# LuMini_2Inch.net
KiCad netlist of a schematic drawn in EAGLE
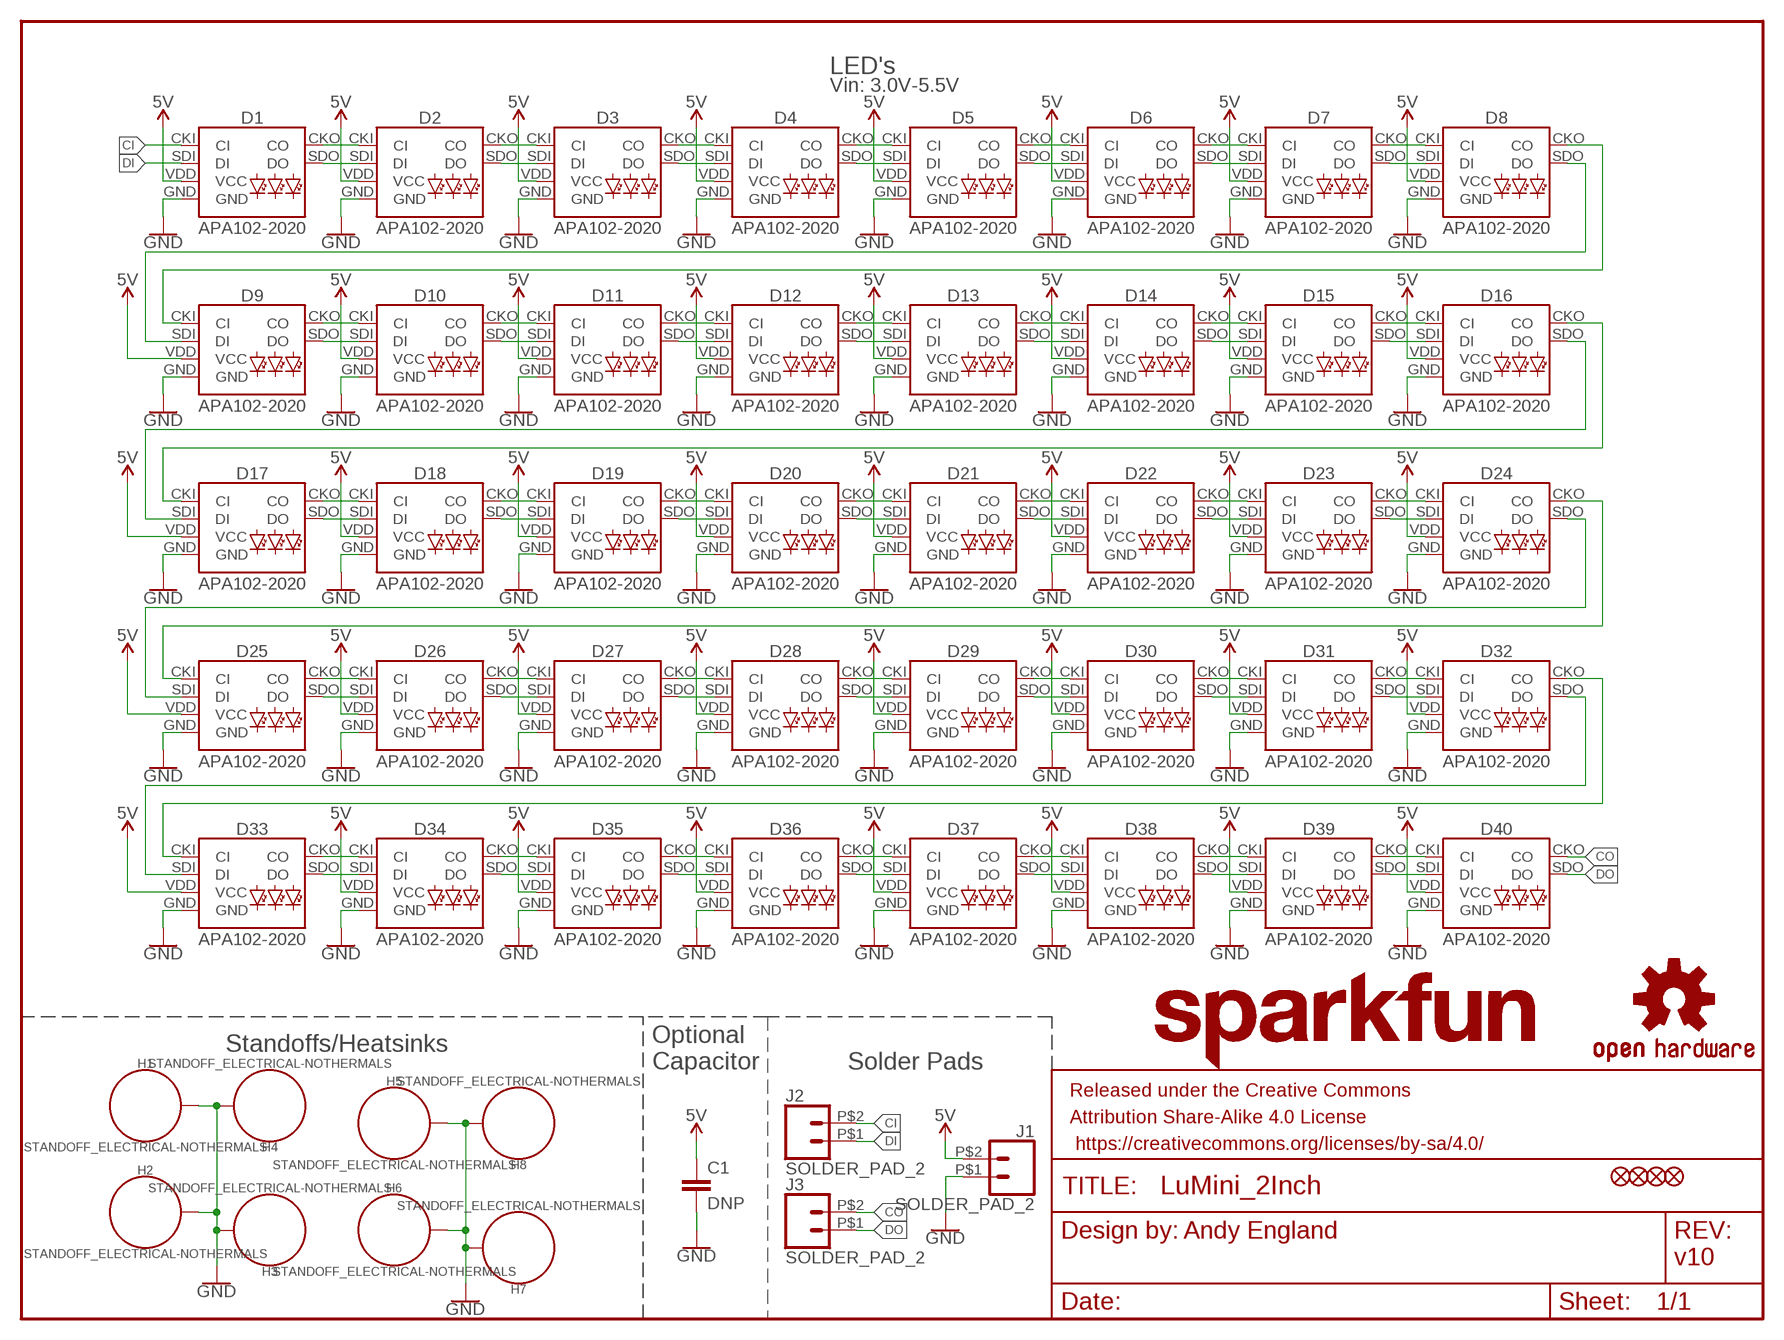
[diagram p0: schematic, sheet 1]

(export (version "E")
  (design (tool "Eeschema 10.0.6"))
  (components
    (comp (ref "C1")
      (value "DNP")
      (footprint "eagle-import:1206")
      (libsource (lib "eagle-import") (part "4.7UF-1206-16V-(+80/-20%)"))
    )
    (comp (ref "D1")
      (value "APA102-2020")
      (footprint "eagle-import:APA102-2020")
      (libsource (lib "eagle-import") (part "APA102-2020"))
    )
    (comp (ref "D2")
      (value "APA102-2020")
      (footprint "eagle-import:APA102-2020")
      (libsource (lib "eagle-import") (part "APA102-2020"))
    )
    (comp (ref "D3")
      (value "APA102-2020")
      (footprint "eagle-import:APA102-2020")
      (libsource (lib "eagle-import") (part "APA102-2020"))
    )
    (comp (ref "D4")
      (value "APA102-2020")
      (footprint "eagle-import:APA102-2020")
      (libsource (lib "eagle-import") (part "APA102-2020"))
    )
    (comp (ref "D5")
      (value "APA102-2020")
      (footprint "eagle-import:APA102-2020")
      (libsource (lib "eagle-import") (part "APA102-2020"))
    )
    (comp (ref "D6")
      (value "APA102-2020")
      (footprint "eagle-import:APA102-2020")
      (libsource (lib "eagle-import") (part "APA102-2020"))
    )
    (comp (ref "D7")
      (value "APA102-2020")
      (footprint "eagle-import:APA102-2020")
      (libsource (lib "eagle-import") (part "APA102-2020"))
    )
    (comp (ref "D8")
      (value "APA102-2020")
      (footprint "eagle-import:APA102-2020")
      (libsource (lib "eagle-import") (part "APA102-2020"))
    )
    (comp (ref "D9")
      (value "APA102-2020")
      (footprint "eagle-import:APA102-2020")
      (libsource (lib "eagle-import") (part "APA102-2020"))
    )
    (comp (ref "D10")
      (value "APA102-2020")
      (footprint "eagle-import:APA102-2020")
      (libsource (lib "eagle-import") (part "APA102-2020"))
    )
    (comp (ref "D11")
      (value "APA102-2020")
      (footprint "eagle-import:APA102-2020")
      (libsource (lib "eagle-import") (part "APA102-2020"))
    )
    (comp (ref "D12")
      (value "APA102-2020")
      (footprint "eagle-import:APA102-2020")
      (libsource (lib "eagle-import") (part "APA102-2020"))
    )
    (comp (ref "D13")
      (value "APA102-2020")
      (footprint "eagle-import:APA102-2020")
      (libsource (lib "eagle-import") (part "APA102-2020"))
    )
    (comp (ref "D14")
      (value "APA102-2020")
      (footprint "eagle-import:APA102-2020")
      (libsource (lib "eagle-import") (part "APA102-2020"))
    )
    (comp (ref "D15")
      (value "APA102-2020")
      (footprint "eagle-import:APA102-2020")
      (libsource (lib "eagle-import") (part "APA102-2020"))
    )
    (comp (ref "D16")
      (value "APA102-2020")
      (footprint "eagle-import:APA102-2020")
      (libsource (lib "eagle-import") (part "APA102-2020"))
    )
    (comp (ref "D17")
      (value "APA102-2020")
      (footprint "eagle-import:APA102-2020")
      (libsource (lib "eagle-import") (part "APA102-2020"))
    )
    (comp (ref "D18")
      (value "APA102-2020")
      (footprint "eagle-import:APA102-2020")
      (libsource (lib "eagle-import") (part "APA102-2020"))
    )
    (comp (ref "D19")
      (value "APA102-2020")
      (footprint "eagle-import:APA102-2020")
      (libsource (lib "eagle-import") (part "APA102-2020"))
    )
    (comp (ref "D20")
      (value "APA102-2020")
      (footprint "eagle-import:APA102-2020")
      (libsource (lib "eagle-import") (part "APA102-2020"))
    )
    (comp (ref "D21")
      (value "APA102-2020")
      (footprint "eagle-import:APA102-2020")
      (libsource (lib "eagle-import") (part "APA102-2020"))
    )
    (comp (ref "D22")
      (value "APA102-2020")
      (footprint "eagle-import:APA102-2020")
      (libsource (lib "eagle-import") (part "APA102-2020"))
    )
    (comp (ref "D23")
      (value "APA102-2020")
      (footprint "eagle-import:APA102-2020")
      (libsource (lib "eagle-import") (part "APA102-2020"))
    )
    (comp (ref "D24")
      (value "APA102-2020")
      (footprint "eagle-import:APA102-2020")
      (libsource (lib "eagle-import") (part "APA102-2020"))
    )
    (comp (ref "D25")
      (value "APA102-2020")
      (footprint "eagle-import:APA102-2020")
      (libsource (lib "eagle-import") (part "APA102-2020"))
    )
    (comp (ref "D26")
      (value "APA102-2020")
      (footprint "eagle-import:APA102-2020")
      (libsource (lib "eagle-import") (part "APA102-2020"))
    )
    (comp (ref "D27")
      (value "APA102-2020")
      (footprint "eagle-import:APA102-2020")
      (libsource (lib "eagle-import") (part "APA102-2020"))
    )
    (comp (ref "D28")
      (value "APA102-2020")
      (footprint "eagle-import:APA102-2020")
      (libsource (lib "eagle-import") (part "APA102-2020"))
    )
    (comp (ref "D29")
      (value "APA102-2020")
      (footprint "eagle-import:APA102-2020")
      (libsource (lib "eagle-import") (part "APA102-2020"))
    )
    (comp (ref "D30")
      (value "APA102-2020")
      (footprint "eagle-import:APA102-2020")
      (libsource (lib "eagle-import") (part "APA102-2020"))
    )
    (comp (ref "D31")
      (value "APA102-2020")
      (footprint "eagle-import:APA102-2020")
      (libsource (lib "eagle-import") (part "APA102-2020"))
    )
    (comp (ref "D32")
      (value "APA102-2020")
      (footprint "eagle-import:APA102-2020")
      (libsource (lib "eagle-import") (part "APA102-2020"))
    )
    (comp (ref "D33")
      (value "APA102-2020")
      (footprint "eagle-import:APA102-2020")
      (libsource (lib "eagle-import") (part "APA102-2020"))
    )
    (comp (ref "D34")
      (value "APA102-2020")
      (footprint "eagle-import:APA102-2020")
      (libsource (lib "eagle-import") (part "APA102-2020"))
    )
    (comp (ref "D35")
      (value "APA102-2020")
      (footprint "eagle-import:APA102-2020")
      (libsource (lib "eagle-import") (part "APA102-2020"))
    )
    (comp (ref "D36")
      (value "APA102-2020")
      (footprint "eagle-import:APA102-2020")
      (libsource (lib "eagle-import") (part "APA102-2020"))
    )
    (comp (ref "D37")
      (value "APA102-2020")
      (footprint "eagle-import:APA102-2020")
      (libsource (lib "eagle-import") (part "APA102-2020"))
    )
    (comp (ref "D38")
      (value "APA102-2020")
      (footprint "eagle-import:APA102-2020")
      (libsource (lib "eagle-import") (part "APA102-2020"))
    )
    (comp (ref "D39")
      (value "APA102-2020")
      (footprint "eagle-import:APA102-2020")
      (libsource (lib "eagle-import") (part "APA102-2020"))
    )
    (comp (ref "D40")
      (value "APA102-2020")
      (footprint "eagle-import:APA102-2020")
      (libsource (lib "eagle-import") (part "APA102-2020"))
    )
    (comp (ref "FD1")
      (value "FIDUCIALUFIDUCIAL")
      (footprint "eagle-import:FIDUCIAL-MICRO")
      (libsource (lib "eagle-import") (part "FIDUCIALUFIDUCIAL"))
    )
    (comp (ref "FD2")
      (value "FIDUCIALUFIDUCIAL")
      (footprint "eagle-import:FIDUCIAL-MICRO")
      (libsource (lib "eagle-import") (part "FIDUCIALUFIDUCIAL"))
    )
    (comp (ref "FD3")
      (value "FIDUCIALUFIDUCIAL")
      (footprint "eagle-import:FIDUCIAL-MICRO")
      (libsource (lib "eagle-import") (part "FIDUCIALUFIDUCIAL"))
    )
    (comp (ref "FD4")
      (value "FIDUCIALUFIDUCIAL")
      (footprint "eagle-import:FIDUCIAL-MICRO")
      (libsource (lib "eagle-import") (part "FIDUCIALUFIDUCIAL"))
    )
    (comp (ref "FRAME1")
      (value "FRAME-LETTER")
      (footprint "eagle-import:CREATIVE_COMMONS")
      (libsource (lib "eagle-import") (part "FRAME-LETTER"))
    )
    (comp (ref "H1")
      (value "STANDOFF_ELECTRICAL-NOTHERMALS")
      (footprint "eagle-import:STANDOFF-ELECTRICAL-NOTHERMALS")
      (libsource (lib "eagle-import") (part "STANDOFF_ELECTRICAL-NOTHERMALS"))
    )
    (comp (ref "H2")
      (value "STANDOFF_ELECTRICAL-NOTHERMALS")
      (footprint "eagle-import:STANDOFF-ELECTRICAL-NOTHERMALS")
      (libsource (lib "eagle-import") (part "STANDOFF_ELECTRICAL-NOTHERMALS"))
    )
    (comp (ref "H3")
      (value "STANDOFF_ELECTRICAL-NOTHERMALS")
      (footprint "eagle-import:STANDOFF-ELECTRICAL-NOTHERMALS")
      (libsource (lib "eagle-import") (part "STANDOFF_ELECTRICAL-NOTHERMALS"))
    )
    (comp (ref "H4")
      (value "STANDOFF_ELECTRICAL-NOTHERMALS")
      (footprint "eagle-import:STANDOFF-ELECTRICAL-NOTHERMALS")
      (libsource (lib "eagle-import") (part "STANDOFF_ELECTRICAL-NOTHERMALS"))
    )
    (comp (ref "H5")
      (value "STANDOFF_ELECTRICAL-NOTHERMALS")
      (footprint "eagle-import:STANDOFF-ELECTRICAL-NOTHERMALS")
      (libsource (lib "eagle-import") (part "STANDOFF_ELECTRICAL-NOTHERMALS"))
    )
    (comp (ref "H6")
      (value "STANDOFF_ELECTRICAL-NOTHERMALS")
      (footprint "eagle-import:STANDOFF-ELECTRICAL-NOTHERMALS")
      (libsource (lib "eagle-import") (part "STANDOFF_ELECTRICAL-NOTHERMALS"))
    )
    (comp (ref "H7")
      (value "STANDOFF_ELECTRICAL-NOTHERMALS")
      (footprint "eagle-import:STANDOFF-ELECTRICAL-NOTHERMALS")
      (libsource (lib "eagle-import") (part "STANDOFF_ELECTRICAL-NOTHERMALS"))
    )
    (comp (ref "H8")
      (value "STANDOFF_ELECTRICAL-NOTHERMALS")
      (footprint "eagle-import:STANDOFF-ELECTRICAL-NOTHERMALS")
      (libsource (lib "eagle-import") (part "STANDOFF_ELECTRICAL-NOTHERMALS"))
    )
    (comp (ref "J1")
      (value "SOLDER_PAD_2")
      (footprint "eagle-import:SOLDER_PAD_2")
      (libsource (lib "eagle-import") (part "SOLDER_PAD_2"))
    )
    (comp (ref "J2")
      (value "SOLDER_PAD_2")
      (footprint "eagle-import:SOLDER_PAD_2")
      (libsource (lib "eagle-import") (part "SOLDER_PAD_2"))
    )
    (comp (ref "J3")
      (value "SOLDER_PAD_2")
      (footprint "eagle-import:SOLDER_PAD_2")
      (libsource (lib "eagle-import") (part "SOLDER_PAD_2"))
    )
    (comp (ref "LOGO1")
      (value "OSHW-LOGOS")
      (footprint "eagle-import:OSHW-LOGO-S")
      (libsource (lib "eagle-import") (part "OSHW-LOGOS"))
    )
    (comp (ref "LOGO2")
      (value "SFE_LOGO_NAME.1_INCH")
      (footprint "eagle-import:SFE_LOGO_NAME_.1")
      (libsource (lib "eagle-import") (part "SFE_LOGO_NAME.1_INCH"))
    )
  )
  (nets
    (net (code "1") (name "5V") (class "Default")
      (node (ref "C1") (pin "1") (pinfunction "1_1") (pintype "passive"))
      (node (ref "D1") (pin "VDD") (pinfunction "VCC_VDD") (pintype "bidirectional"))
      (node (ref "D10") (pin "VDD") (pinfunction "VCC_VDD") (pintype "bidirectional"))
      (node (ref "D11") (pin "VDD") (pinfunction "VCC_VDD") (pintype "bidirectional"))
      (node (ref "D12") (pin "VDD") (pinfunction "VCC_VDD") (pintype "bidirectional"))
      (node (ref "D13") (pin "VDD") (pinfunction "VCC_VDD") (pintype "bidirectional"))
      (node (ref "D14") (pin "VDD") (pinfunction "VCC_VDD") (pintype "bidirectional"))
      (node (ref "D15") (pin "VDD") (pinfunction "VCC_VDD") (pintype "bidirectional"))
      (node (ref "D16") (pin "VDD") (pinfunction "VCC_VDD") (pintype "bidirectional"))
      (node (ref "D17") (pin "VDD") (pinfunction "VCC_VDD") (pintype "bidirectional"))
      (node (ref "D18") (pin "VDD") (pinfunction "VCC_VDD") (pintype "bidirectional"))
      (node (ref "D19") (pin "VDD") (pinfunction "VCC_VDD") (pintype "bidirectional"))
      (node (ref "D2") (pin "VDD") (pinfunction "VCC_VDD") (pintype "bidirectional"))
      (node (ref "D20") (pin "VDD") (pinfunction "VCC_VDD") (pintype "bidirectional"))
      (node (ref "D21") (pin "VDD") (pinfunction "VCC_VDD") (pintype "bidirectional"))
      (node (ref "D22") (pin "VDD") (pinfunction "VCC_VDD") (pintype "bidirectional"))
      (node (ref "D23") (pin "VDD") (pinfunction "VCC_VDD") (pintype "bidirectional"))
      (node (ref "D24") (pin "VDD") (pinfunction "VCC_VDD") (pintype "bidirectional"))
      (node (ref "D25") (pin "VDD") (pinfunction "VCC_VDD") (pintype "bidirectional"))
      (node (ref "D26") (pin "VDD") (pinfunction "VCC_VDD") (pintype "bidirectional"))
      (node (ref "D27") (pin "VDD") (pinfunction "VCC_VDD") (pintype "bidirectional"))
      (node (ref "D28") (pin "VDD") (pinfunction "VCC_VDD") (pintype "bidirectional"))
      (node (ref "D29") (pin "VDD") (pinfunction "VCC_VDD") (pintype "bidirectional"))
      (node (ref "D3") (pin "VDD") (pinfunction "VCC_VDD") (pintype "bidirectional"))
      (node (ref "D30") (pin "VDD") (pinfunction "VCC_VDD") (pintype "bidirectional"))
      (node (ref "D31") (pin "VDD") (pinfunction "VCC_VDD") (pintype "bidirectional"))
      (node (ref "D32") (pin "VDD") (pinfunction "VCC_VDD") (pintype "bidirectional"))
      (node (ref "D33") (pin "VDD") (pinfunction "VCC_VDD") (pintype "bidirectional"))
      (node (ref "D34") (pin "VDD") (pinfunction "VCC_VDD") (pintype "bidirectional"))
      (node (ref "D35") (pin "VDD") (pinfunction "VCC_VDD") (pintype "bidirectional"))
      (node (ref "D36") (pin "VDD") (pinfunction "VCC_VDD") (pintype "bidirectional"))
      (node (ref "D37") (pin "VDD") (pinfunction "VCC_VDD") (pintype "bidirectional"))
      (node (ref "D38") (pin "VDD") (pinfunction "VCC_VDD") (pintype "bidirectional"))
      (node (ref "D39") (pin "VDD") (pinfunction "VCC_VDD") (pintype "bidirectional"))
      (node (ref "D4") (pin "VDD") (pinfunction "VCC_VDD") (pintype "bidirectional"))
      (node (ref "D40") (pin "VDD") (pinfunction "VCC_VDD") (pintype "bidirectional"))
      (node (ref "D5") (pin "VDD") (pinfunction "VCC_VDD") (pintype "bidirectional"))
      (node (ref "D6") (pin "VDD") (pinfunction "VCC_VDD") (pintype "bidirectional"))
      (node (ref "D7") (pin "VDD") (pinfunction "VCC_VDD") (pintype "bidirectional"))
      (node (ref "D8") (pin "VDD") (pinfunction "VCC_VDD") (pintype "bidirectional"))
      (node (ref "D9") (pin "VDD") (pinfunction "VCC_VDD") (pintype "bidirectional"))
      (node (ref "J1") (pin "P$2") (pinfunction "2_P$2") (pintype "passive"))
    )
    (net (code "2") (name "CI") (class "Default")
      (node (ref "D1") (pin "CKI") (pinfunction "CI_CKI") (pintype "bidirectional"))
      (node (ref "J2") (pin "P$2") (pinfunction "2_P$2") (pintype "passive"))
    )
    (net (code "3") (name "CO") (class "Default")
      (node (ref "D40") (pin "CKO") (pinfunction "CO_CKO") (pintype "bidirectional"))
      (node (ref "J3") (pin "P$2") (pinfunction "2_P$2") (pintype "passive"))
    )
    (net (code "4") (name "DI") (class "Default")
      (node (ref "D1") (pin "SDI") (pinfunction "DI_SDI") (pintype "bidirectional"))
      (node (ref "J2") (pin "P$1") (pinfunction "1_P$1") (pintype "passive"))
    )
    (net (code "5") (name "DO") (class "Default")
      (node (ref "D40") (pin "SDO") (pinfunction "DO_SDO") (pintype "bidirectional"))
      (node (ref "J3") (pin "P$1") (pinfunction "1_P$1") (pintype "passive"))
    )
    (net (code "6") (name "GND") (class "Default")
      (node (ref "C1") (pin "2") (pinfunction "2_2") (pintype "passive"))
      (node (ref "D1") (pin "GND") (pinfunction "GND_GND") (pintype "bidirectional"))
      (node (ref "D10") (pin "GND") (pinfunction "GND_GND") (pintype "bidirectional"))
      (node (ref "D11") (pin "GND") (pinfunction "GND_GND") (pintype "bidirectional"))
      (node (ref "D12") (pin "GND") (pinfunction "GND_GND") (pintype "bidirectional"))
      (node (ref "D13") (pin "GND") (pinfunction "GND_GND") (pintype "bidirectional"))
      (node (ref "D14") (pin "GND") (pinfunction "GND_GND") (pintype "bidirectional"))
      (node (ref "D15") (pin "GND") (pinfunction "GND_GND") (pintype "bidirectional"))
      (node (ref "D16") (pin "GND") (pinfunction "GND_GND") (pintype "bidirectional"))
      (node (ref "D17") (pin "GND") (pinfunction "GND_GND") (pintype "bidirectional"))
      (node (ref "D18") (pin "GND") (pinfunction "GND_GND") (pintype "bidirectional"))
      (node (ref "D19") (pin "GND") (pinfunction "GND_GND") (pintype "bidirectional"))
      (node (ref "D2") (pin "GND") (pinfunction "GND_GND") (pintype "bidirectional"))
      (node (ref "D20") (pin "GND") (pinfunction "GND_GND") (pintype "bidirectional"))
      (node (ref "D21") (pin "GND") (pinfunction "GND_GND") (pintype "bidirectional"))
      (node (ref "D22") (pin "GND") (pinfunction "GND_GND") (pintype "bidirectional"))
      (node (ref "D23") (pin "GND") (pinfunction "GND_GND") (pintype "bidirectional"))
      (node (ref "D24") (pin "GND") (pinfunction "GND_GND") (pintype "bidirectional"))
      (node (ref "D25") (pin "GND") (pinfunction "GND_GND") (pintype "bidirectional"))
      (node (ref "D26") (pin "GND") (pinfunction "GND_GND") (pintype "bidirectional"))
      (node (ref "D27") (pin "GND") (pinfunction "GND_GND") (pintype "bidirectional"))
      (node (ref "D28") (pin "GND") (pinfunction "GND_GND") (pintype "bidirectional"))
      (node (ref "D29") (pin "GND") (pinfunction "GND_GND") (pintype "bidirectional"))
      (node (ref "D3") (pin "GND") (pinfunction "GND_GND") (pintype "bidirectional"))
      (node (ref "D30") (pin "GND") (pinfunction "GND_GND") (pintype "bidirectional"))
      (node (ref "D31") (pin "GND") (pinfunction "GND_GND") (pintype "bidirectional"))
      (node (ref "D32") (pin "GND") (pinfunction "GND_GND") (pintype "bidirectional"))
      (node (ref "D33") (pin "GND") (pinfunction "GND_GND") (pintype "bidirectional"))
      (node (ref "D34") (pin "GND") (pinfunction "GND_GND") (pintype "bidirectional"))
      (node (ref "D35") (pin "GND") (pinfunction "GND_GND") (pintype "bidirectional"))
      (node (ref "D36") (pin "GND") (pinfunction "GND_GND") (pintype "bidirectional"))
      (node (ref "D37") (pin "GND") (pinfunction "GND_GND") (pintype "bidirectional"))
      (node (ref "D38") (pin "GND") (pinfunction "GND_GND") (pintype "bidirectional"))
      (node (ref "D39") (pin "GND") (pinfunction "GND_GND") (pintype "bidirectional"))
      (node (ref "D4") (pin "GND") (pinfunction "GND_GND") (pintype "bidirectional"))
      (node (ref "D40") (pin "GND") (pinfunction "GND_GND") (pintype "bidirectional"))
      (node (ref "D5") (pin "GND") (pinfunction "GND_GND") (pintype "bidirectional"))
      (node (ref "D6") (pin "GND") (pinfunction "GND_GND") (pintype "bidirectional"))
      (node (ref "D7") (pin "GND") (pinfunction "GND_GND") (pintype "bidirectional"))
      (node (ref "D8") (pin "GND") (pinfunction "GND_GND") (pintype "bidirectional"))
      (node (ref "D9") (pin "GND") (pinfunction "GND_GND") (pintype "bidirectional"))
      (node (ref "H1") (pin "P1") (pinfunction "P$1_P1") (pintype "bidirectional"))
      (node (ref "H2") (pin "P1") (pinfunction "P$1_P1") (pintype "bidirectional"))
      (node (ref "H3") (pin "P1") (pinfunction "P$1_P1") (pintype "bidirectional"))
      (node (ref "H4") (pin "P1") (pinfunction "P$1_P1") (pintype "bidirectional"))
      (node (ref "H5") (pin "P1") (pinfunction "P$1_P1") (pintype "bidirectional"))
      (node (ref "H6") (pin "P1") (pinfunction "P$1_P1") (pintype "bidirectional"))
      (node (ref "H7") (pin "P1") (pinfunction "P$1_P1") (pintype "bidirectional"))
      (node (ref "H8") (pin "P1") (pinfunction "P$1_P1") (pintype "bidirectional"))
      (node (ref "J1") (pin "P$1") (pinfunction "1_P$1") (pintype "passive"))
    )
    (net (code "7") (name "Net-(D1-CO)") (class "Default")
      (node (ref "D1") (pin "CKO") (pinfunction "CO_CKO") (pintype "bidirectional"))
      (node (ref "D2") (pin "CKI") (pinfunction "CI_CKI") (pintype "bidirectional"))
    )
    (net (code "8") (name "Net-(D1-DO)") (class "Default")
      (node (ref "D1") (pin "SDO") (pinfunction "DO_SDO") (pintype "bidirectional"))
      (node (ref "D2") (pin "SDI") (pinfunction "DI_SDI") (pintype "bidirectional"))
    )
    (net (code "9") (name "Net-(D2-CO)") (class "Default")
      (node (ref "D2") (pin "CKO") (pinfunction "CO_CKO") (pintype "bidirectional"))
      (node (ref "D3") (pin "CKI") (pinfunction "CI_CKI") (pintype "bidirectional"))
    )
    (net (code "10") (name "Net-(D2-DO)") (class "Default")
      (node (ref "D2") (pin "SDO") (pinfunction "DO_SDO") (pintype "bidirectional"))
      (node (ref "D3") (pin "SDI") (pinfunction "DI_SDI") (pintype "bidirectional"))
    )
    (net (code "11") (name "Net-(D3-CO)") (class "Default")
      (node (ref "D3") (pin "CKO") (pinfunction "CO_CKO") (pintype "bidirectional"))
      (node (ref "D4") (pin "CKI") (pinfunction "CI_CKI") (pintype "bidirectional"))
    )
    (net (code "12") (name "Net-(D3-DO)") (class "Default")
      (node (ref "D3") (pin "SDO") (pinfunction "DO_SDO") (pintype "bidirectional"))
      (node (ref "D4") (pin "SDI") (pinfunction "DI_SDI") (pintype "bidirectional"))
    )
    (net (code "13") (name "Net-(D4-CO)") (class "Default")
      (node (ref "D4") (pin "CKO") (pinfunction "CO_CKO") (pintype "bidirectional"))
      (node (ref "D5") (pin "CKI") (pinfunction "CI_CKI") (pintype "bidirectional"))
    )
    (net (code "14") (name "Net-(D4-DO)") (class "Default")
      (node (ref "D4") (pin "SDO") (pinfunction "DO_SDO") (pintype "bidirectional"))
      (node (ref "D5") (pin "SDI") (pinfunction "DI_SDI") (pintype "bidirectional"))
    )
    (net (code "15") (name "Net-(D5-CO)") (class "Default")
      (node (ref "D5") (pin "CKO") (pinfunction "CO_CKO") (pintype "bidirectional"))
      (node (ref "D6") (pin "CKI") (pinfunction "CI_CKI") (pintype "bidirectional"))
    )
    (net (code "16") (name "Net-(D5-DO)") (class "Default")
      (node (ref "D5") (pin "SDO") (pinfunction "DO_SDO") (pintype "bidirectional"))
      (node (ref "D6") (pin "SDI") (pinfunction "DI_SDI") (pintype "bidirectional"))
    )
    (net (code "17") (name "Net-(D6-CO)") (class "Default")
      (node (ref "D6") (pin "CKO") (pinfunction "CO_CKO") (pintype "bidirectional"))
      (node (ref "D7") (pin "CKI") (pinfunction "CI_CKI") (pintype "bidirectional"))
    )
    (net (code "18") (name "Net-(D6-DO)") (class "Default")
      (node (ref "D6") (pin "SDO") (pinfunction "DO_SDO") (pintype "bidirectional"))
      (node (ref "D7") (pin "SDI") (pinfunction "DI_SDI") (pintype "bidirectional"))
    )
    (net (code "19") (name "Net-(D7-CO)") (class "Default")
      (node (ref "D7") (pin "CKO") (pinfunction "CO_CKO") (pintype "bidirectional"))
      (node (ref "D8") (pin "CKI") (pinfunction "CI_CKI") (pintype "bidirectional"))
    )
    (net (code "20") (name "Net-(D7-DO)") (class "Default")
      (node (ref "D7") (pin "SDO") (pinfunction "DO_SDO") (pintype "bidirectional"))
      (node (ref "D8") (pin "SDI") (pinfunction "DI_SDI") (pintype "bidirectional"))
    )
    (net (code "21") (name "Net-(D8-CO)") (class "Default")
      (node (ref "D8") (pin "CKO") (pinfunction "CO_CKO") (pintype "bidirectional"))
      (node (ref "D9") (pin "CKI") (pinfunction "CI_CKI") (pintype "bidirectional"))
    )
    (net (code "22") (name "Net-(D8-DO)") (class "Default")
      (node (ref "D8") (pin "SDO") (pinfunction "DO_SDO") (pintype "bidirectional"))
      (node (ref "D9") (pin "SDI") (pinfunction "DI_SDI") (pintype "bidirectional"))
    )
    (net (code "23") (name "Net-(D10-CI)") (class "Default")
      (node (ref "D10") (pin "CKI") (pinfunction "CI_CKI") (pintype "bidirectional"))
      (node (ref "D9") (pin "CKO") (pinfunction "CO_CKO") (pintype "bidirectional"))
    )
    (net (code "24") (name "Net-(D10-CO)") (class "Default")
      (node (ref "D10") (pin "CKO") (pinfunction "CO_CKO") (pintype "bidirectional"))
      (node (ref "D11") (pin "CKI") (pinfunction "CI_CKI") (pintype "bidirectional"))
    )
    (net (code "25") (name "Net-(D10-DI)") (class "Default")
      (node (ref "D10") (pin "SDI") (pinfunction "DI_SDI") (pintype "bidirectional"))
      (node (ref "D9") (pin "SDO") (pinfunction "DO_SDO") (pintype "bidirectional"))
    )
    (net (code "26") (name "Net-(D10-DO)") (class "Default")
      (node (ref "D10") (pin "SDO") (pinfunction "DO_SDO") (pintype "bidirectional"))
      (node (ref "D11") (pin "SDI") (pinfunction "DI_SDI") (pintype "bidirectional"))
    )
    (net (code "27") (name "Net-(D11-CO)") (class "Default")
      (node (ref "D11") (pin "CKO") (pinfunction "CO_CKO") (pintype "bidirectional"))
      (node (ref "D12") (pin "CKI") (pinfunction "CI_CKI") (pintype "bidirectional"))
    )
    (net (code "28") (name "Net-(D11-DO)") (class "Default")
      (node (ref "D11") (pin "SDO") (pinfunction "DO_SDO") (pintype "bidirectional"))
      (node (ref "D12") (pin "SDI") (pinfunction "DI_SDI") (pintype "bidirectional"))
    )
    (net (code "29") (name "Net-(D12-CO)") (class "Default")
      (node (ref "D12") (pin "CKO") (pinfunction "CO_CKO") (pintype "bidirectional"))
      (node (ref "D13") (pin "CKI") (pinfunction "CI_CKI") (pintype "bidirectional"))
    )
    (net (code "30") (name "Net-(D12-DO)") (class "Default")
      (node (ref "D12") (pin "SDO") (pinfunction "DO_SDO") (pintype "bidirectional"))
      (node (ref "D13") (pin "SDI") (pinfunction "DI_SDI") (pintype "bidirectional"))
    )
    (net (code "31") (name "Net-(D13-CO)") (class "Default")
      (node (ref "D13") (pin "CKO") (pinfunction "CO_CKO") (pintype "bidirectional"))
      (node (ref "D14") (pin "CKI") (pinfunction "CI_CKI") (pintype "bidirectional"))
    )
    (net (code "32") (name "Net-(D13-DO)") (class "Default")
      (node (ref "D13") (pin "SDO") (pinfunction "DO_SDO") (pintype "bidirectional"))
      (node (ref "D14") (pin "SDI") (pinfunction "DI_SDI") (pintype "bidirectional"))
    )
    (net (code "33") (name "Net-(D14-CO)") (class "Default")
      (node (ref "D14") (pin "CKO") (pinfunction "CO_CKO") (pintype "bidirectional"))
      (node (ref "D15") (pin "CKI") (pinfunction "CI_CKI") (pintype "bidirectional"))
    )
    (net (code "34") (name "Net-(D14-DO)") (class "Default")
      (node (ref "D14") (pin "SDO") (pinfunction "DO_SDO") (pintype "bidirectional"))
      (node (ref "D15") (pin "SDI") (pinfunction "DI_SDI") (pintype "bidirectional"))
    )
    (net (code "35") (name "Net-(D15-CO)") (class "Default")
      (node (ref "D15") (pin "CKO") (pinfunction "CO_CKO") (pintype "bidirectional"))
      (node (ref "D16") (pin "CKI") (pinfunction "CI_CKI") (pintype "bidirectional"))
    )
    (net (code "36") (name "Net-(D15-DO)") (class "Default")
      (node (ref "D15") (pin "SDO") (pinfunction "DO_SDO") (pintype "bidirectional"))
      (node (ref "D16") (pin "SDI") (pinfunction "DI_SDI") (pintype "bidirectional"))
    )
    (net (code "37") (name "Net-(D16-CO)") (class "Default")
      (node (ref "D16") (pin "CKO") (pinfunction "CO_CKO") (pintype "bidirectional"))
      (node (ref "D17") (pin "CKI") (pinfunction "CI_CKI") (pintype "bidirectional"))
    )
    (net (code "38") (name "Net-(D16-DO)") (class "Default")
      (node (ref "D16") (pin "SDO") (pinfunction "DO_SDO") (pintype "bidirectional"))
      (node (ref "D17") (pin "SDI") (pinfunction "DI_SDI") (pintype "bidirectional"))
    )
    (net (code "39") (name "Net-(D17-CO)") (class "Default")
      (node (ref "D17") (pin "CKO") (pinfunction "CO_CKO") (pintype "bidirectional"))
      (node (ref "D18") (pin "CKI") (pinfunction "CI_CKI") (pintype "bidirectional"))
    )
    (net (code "40") (name "Net-(D17-DO)") (class "Default")
      (node (ref "D17") (pin "SDO") (pinfunction "DO_SDO") (pintype "bidirectional"))
      (node (ref "D18") (pin "SDI") (pinfunction "DI_SDI") (pintype "bidirectional"))
    )
    (net (code "41") (name "Net-(D18-CO)") (class "Default")
      (node (ref "D18") (pin "CKO") (pinfunction "CO_CKO") (pintype "bidirectional"))
      (node (ref "D19") (pin "CKI") (pinfunction "CI_CKI") (pintype "bidirectional"))
    )
    (net (code "42") (name "Net-(D18-DO)") (class "Default")
      (node (ref "D18") (pin "SDO") (pinfunction "DO_SDO") (pintype "bidirectional"))
      (node (ref "D19") (pin "SDI") (pinfunction "DI_SDI") (pintype "bidirectional"))
    )
    (net (code "43") (name "Net-(D19-CO)") (class "Default")
      (node (ref "D19") (pin "CKO") (pinfunction "CO_CKO") (pintype "bidirectional"))
      (node (ref "D20") (pin "CKI") (pinfunction "CI_CKI") (pintype "bidirectional"))
    )
    (net (code "44") (name "Net-(D19-DO)") (class "Default")
      (node (ref "D19") (pin "SDO") (pinfunction "DO_SDO") (pintype "bidirectional"))
      (node (ref "D20") (pin "SDI") (pinfunction "DI_SDI") (pintype "bidirectional"))
    )
    (net (code "45") (name "Net-(D20-CO)") (class "Default")
      (node (ref "D20") (pin "CKO") (pinfunction "CO_CKO") (pintype "bidirectional"))
      (node (ref "D21") (pin "CKI") (pinfunction "CI_CKI") (pintype "bidirectional"))
    )
    (net (code "46") (name "Net-(D20-DO)") (class "Default")
      (node (ref "D20") (pin "SDO") (pinfunction "DO_SDO") (pintype "bidirectional"))
      (node (ref "D21") (pin "SDI") (pinfunction "DI_SDI") (pintype "bidirectional"))
    )
    (net (code "47") (name "Net-(D21-CO)") (class "Default")
      (node (ref "D21") (pin "CKO") (pinfunction "CO_CKO") (pintype "bidirectional"))
      (node (ref "D22") (pin "CKI") (pinfunction "CI_CKI") (pintype "bidirectional"))
    )
    (net (code "48") (name "Net-(D21-DO)") (class "Default")
      (node (ref "D21") (pin "SDO") (pinfunction "DO_SDO") (pintype "bidirectional"))
      (node (ref "D22") (pin "SDI") (pinfunction "DI_SDI") (pintype "bidirectional"))
    )
    (net (code "49") (name "Net-(D22-CO)") (class "Default")
      (node (ref "D22") (pin "CKO") (pinfunction "CO_CKO") (pintype "bidirectional"))
      (node (ref "D23") (pin "CKI") (pinfunction "CI_CKI") (pintype "bidirectional"))
    )
    (net (code "50") (name "Net-(D22-DO)") (class "Default")
      (node (ref "D22") (pin "SDO") (pinfunction "DO_SDO") (pintype "bidirectional"))
      (node (ref "D23") (pin "SDI") (pinfunction "DI_SDI") (pintype "bidirectional"))
    )
    (net (code "51") (name "Net-(D23-CO)") (class "Default")
      (node (ref "D23") (pin "CKO") (pinfunction "CO_CKO") (pintype "bidirectional"))
      (node (ref "D24") (pin "CKI") (pinfunction "CI_CKI") (pintype "bidirectional"))
    )
    (net (code "52") (name "Net-(D23-DO)") (class "Default")
      (node (ref "D23") (pin "SDO") (pinfunction "DO_SDO") (pintype "bidirectional"))
      (node (ref "D24") (pin "SDI") (pinfunction "DI_SDI") (pintype "bidirectional"))
    )
    (net (code "53") (name "Net-(D24-CO)") (class "Default")
      (node (ref "D24") (pin "CKO") (pinfunction "CO_CKO") (pintype "bidirectional"))
      (node (ref "D25") (pin "CKI") (pinfunction "CI_CKI") (pintype "bidirectional"))
    )
    (net (code "54") (name "Net-(D24-DO)") (class "Default")
      (node (ref "D24") (pin "SDO") (pinfunction "DO_SDO") (pintype "bidirectional"))
      (node (ref "D25") (pin "SDI") (pinfunction "DI_SDI") (pintype "bidirectional"))
    )
    (net (code "55") (name "Net-(D25-CO)") (class "Default")
      (node (ref "D25") (pin "CKO") (pinfunction "CO_CKO") (pintype "bidirectional"))
      (node (ref "D26") (pin "CKI") (pinfunction "CI_CKI") (pintype "bidirectional"))
    )
    (net (code "56") (name "Net-(D25-DO)") (class "Default")
      (node (ref "D25") (pin "SDO") (pinfunction "DO_SDO") (pintype "bidirectional"))
      (node (ref "D26") (pin "SDI") (pinfunction "DI_SDI") (pintype "bidirectional"))
    )
    (net (code "57") (name "Net-(D26-CO)") (class "Default")
      (node (ref "D26") (pin "CKO") (pinfunction "CO_CKO") (pintype "bidirectional"))
      (node (ref "D27") (pin "CKI") (pinfunction "CI_CKI") (pintype "bidirectional"))
    )
    (net (code "58") (name "Net-(D26-DO)") (class "Default")
      (node (ref "D26") (pin "SDO") (pinfunction "DO_SDO") (pintype "bidirectional"))
      (node (ref "D27") (pin "SDI") (pinfunction "DI_SDI") (pintype "bidirectional"))
    )
    (net (code "59") (name "Net-(D27-CO)") (class "Default")
      (node (ref "D27") (pin "CKO") (pinfunction "CO_CKO") (pintype "bidirectional"))
      (node (ref "D28") (pin "CKI") (pinfunction "CI_CKI") (pintype "bidirectional"))
    )
    (net (code "60") (name "Net-(D27-DO)") (class "Default")
      (node (ref "D27") (pin "SDO") (pinfunction "DO_SDO") (pintype "bidirectional"))
      (node (ref "D28") (pin "SDI") (pinfunction "DI_SDI") (pintype "bidirectional"))
    )
    (net (code "61") (name "Net-(D28-CO)") (class "Default")
      (node (ref "D28") (pin "CKO") (pinfunction "CO_CKO") (pintype "bidirectional"))
      (node (ref "D29") (pin "CKI") (pinfunction "CI_CKI") (pintype "bidirectional"))
    )
    (net (code "62") (name "Net-(D28-DO)") (class "Default")
      (node (ref "D28") (pin "SDO") (pinfunction "DO_SDO") (pintype "bidirectional"))
      (node (ref "D29") (pin "SDI") (pinfunction "DI_SDI") (pintype "bidirectional"))
    )
    (net (code "63") (name "Net-(D29-CO)") (class "Default")
      (node (ref "D29") (pin "CKO") (pinfunction "CO_CKO") (pintype "bidirectional"))
      (node (ref "D30") (pin "CKI") (pinfunction "CI_CKI") (pintype "bidirectional"))
    )
    (net (code "64") (name "Net-(D29-DO)") (class "Default")
      (node (ref "D29") (pin "SDO") (pinfunction "DO_SDO") (pintype "bidirectional"))
      (node (ref "D30") (pin "SDI") (pinfunction "DI_SDI") (pintype "bidirectional"))
    )
    (net (code "65") (name "Net-(D30-CO)") (class "Default")
      (node (ref "D30") (pin "CKO") (pinfunction "CO_CKO") (pintype "bidirectional"))
      (node (ref "D31") (pin "CKI") (pinfunction "CI_CKI") (pintype "bidirectional"))
    )
    (net (code "66") (name "Net-(D30-DO)") (class "Default")
      (node (ref "D30") (pin "SDO") (pinfunction "DO_SDO") (pintype "bidirectional"))
      (node (ref "D31") (pin "SDI") (pinfunction "DI_SDI") (pintype "bidirectional"))
    )
    (net (code "67") (name "Net-(D31-CO)") (class "Default")
      (node (ref "D31") (pin "CKO") (pinfunction "CO_CKO") (pintype "bidirectional"))
      (node (ref "D32") (pin "CKI") (pinfunction "CI_CKI") (pintype "bidirectional"))
    )
    (net (code "68") (name "Net-(D31-DO)") (class "Default")
      (node (ref "D31") (pin "SDO") (pinfunction "DO_SDO") (pintype "bidirectional"))
      (node (ref "D32") (pin "SDI") (pinfunction "DI_SDI") (pintype "bidirectional"))
    )
    (net (code "69") (name "Net-(D32-CO)") (class "Default")
      (node (ref "D32") (pin "CKO") (pinfunction "CO_CKO") (pintype "bidirectional"))
      (node (ref "D33") (pin "CKI") (pinfunction "CI_CKI") (pintype "bidirectional"))
    )
    (net (code "70") (name "Net-(D32-DO)") (class "Default")
      (node (ref "D32") (pin "SDO") (pinfunction "DO_SDO") (pintype "bidirectional"))
      (node (ref "D33") (pin "SDI") (pinfunction "DI_SDI") (pintype "bidirectional"))
    )
    (net (code "71") (name "Net-(D33-CO)") (class "Default")
      (node (ref "D33") (pin "CKO") (pinfunction "CO_CKO") (pintype "bidirectional"))
      (node (ref "D34") (pin "CKI") (pinfunction "CI_CKI") (pintype "bidirectional"))
    )
    (net (code "72") (name "Net-(D33-DO)") (class "Default")
      (node (ref "D33") (pin "SDO") (pinfunction "DO_SDO") (pintype "bidirectional"))
      (node (ref "D34") (pin "SDI") (pinfunction "DI_SDI") (pintype "bidirectional"))
    )
    (net (code "73") (name "Net-(D34-CO)") (class "Default")
      (node (ref "D34") (pin "CKO") (pinfunction "CO_CKO") (pintype "bidirectional"))
      (node (ref "D35") (pin "CKI") (pinfunction "CI_CKI") (pintype "bidirectional"))
    )
    (net (code "74") (name "Net-(D34-DO)") (class "Default")
      (node (ref "D34") (pin "SDO") (pinfunction "DO_SDO") (pintype "bidirectional"))
      (node (ref "D35") (pin "SDI") (pinfunction "DI_SDI") (pintype "bidirectional"))
    )
    (net (code "75") (name "Net-(D35-CO)") (class "Default")
      (node (ref "D35") (pin "CKO") (pinfunction "CO_CKO") (pintype "bidirectional"))
      (node (ref "D36") (pin "CKI") (pinfunction "CI_CKI") (pintype "bidirectional"))
    )
    (net (code "76") (name "Net-(D35-DO)") (class "Default")
      (node (ref "D35") (pin "SDO") (pinfunction "DO_SDO") (pintype "bidirectional"))
      (node (ref "D36") (pin "SDI") (pinfunction "DI_SDI") (pintype "bidirectional"))
    )
    (net (code "77") (name "Net-(D36-CO)") (class "Default")
      (node (ref "D36") (pin "CKO") (pinfunction "CO_CKO") (pintype "bidirectional"))
      (node (ref "D37") (pin "CKI") (pinfunction "CI_CKI") (pintype "bidirectional"))
    )
    (net (code "78") (name "Net-(D36-DO)") (class "Default")
      (node (ref "D36") (pin "SDO") (pinfunction "DO_SDO") (pintype "bidirectional"))
      (node (ref "D37") (pin "SDI") (pinfunction "DI_SDI") (pintype "bidirectional"))
    )
    (net (code "79") (name "Net-(D37-CO)") (class "Default")
      (node (ref "D37") (pin "CKO") (pinfunction "CO_CKO") (pintype "bidirectional"))
      (node (ref "D38") (pin "CKI") (pinfunction "CI_CKI") (pintype "bidirectional"))
    )
    (net (code "80") (name "Net-(D37-DO)") (class "Default")
      (node (ref "D37") (pin "SDO") (pinfunction "DO_SDO") (pintype "bidirectional"))
      (node (ref "D38") (pin "SDI") (pinfunction "DI_SDI") (pintype "bidirectional"))
    )
    (net (code "81") (name "Net-(D38-CO)") (class "Default")
      (node (ref "D38") (pin "CKO") (pinfunction "CO_CKO") (pintype "bidirectional"))
      (node (ref "D39") (pin "CKI") (pinfunction "CI_CKI") (pintype "bidirectional"))
    )
    (net (code "82") (name "Net-(D38-DO)") (class "Default")
      (node (ref "D38") (pin "SDO") (pinfunction "DO_SDO") (pintype "bidirectional"))
      (node (ref "D39") (pin "SDI") (pinfunction "DI_SDI") (pintype "bidirectional"))
    )
    (net (code "83") (name "Net-(D39-CO)") (class "Default")
      (node (ref "D39") (pin "CKO") (pinfunction "CO_CKO") (pintype "bidirectional"))
      (node (ref "D40") (pin "CKI") (pinfunction "CI_CKI") (pintype "bidirectional"))
    )
    (net (code "84") (name "Net-(D39-DO)") (class "Default")
      (node (ref "D39") (pin "SDO") (pinfunction "DO_SDO") (pintype "bidirectional"))
      (node (ref "D40") (pin "SDI") (pinfunction "DI_SDI") (pintype "bidirectional"))
    )
  )
)
